# Si5351.net
KiCad netlist of a schematic drawn in EAGLE
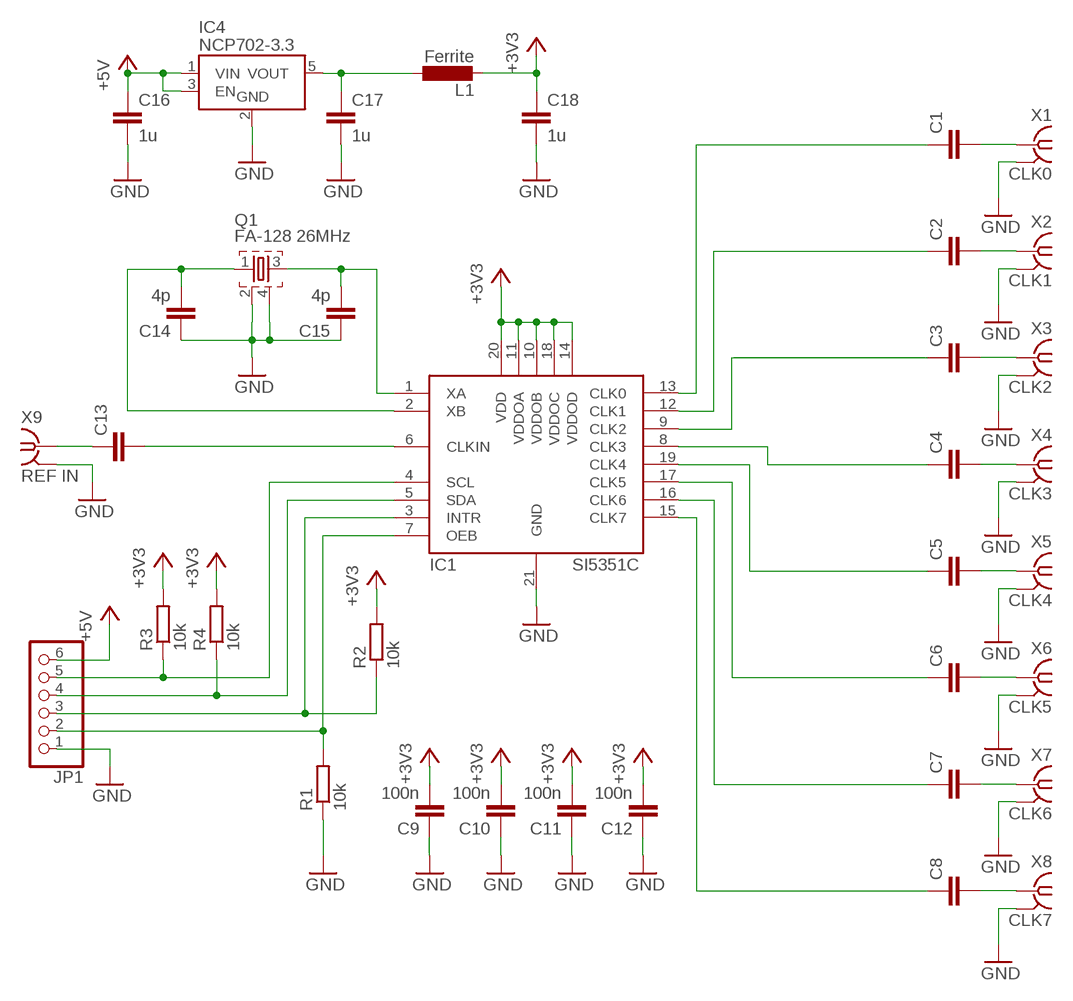
[diagram p0: schematic, sheet 1]

(export (version "E")
  (design (tool "Eeschema 10.0.6"))
  (components
    (comp (ref "C1")
      (value "C-EUC0603")
      (footprint "eagle-import:C0603")
      (libsource (lib "eagle-import") (part "C-EUC0603"))
    )
    (comp (ref "C2")
      (value "C-EUC0603")
      (footprint "eagle-import:C0603")
      (libsource (lib "eagle-import") (part "C-EUC0603"))
    )
    (comp (ref "C3")
      (value "C-EUC0603")
      (footprint "eagle-import:C0603")
      (libsource (lib "eagle-import") (part "C-EUC0603"))
    )
    (comp (ref "C4")
      (value "C-EUC0603")
      (footprint "eagle-import:C0603")
      (libsource (lib "eagle-import") (part "C-EUC0603"))
    )
    (comp (ref "C5")
      (value "C-EUC0603")
      (footprint "eagle-import:C0603")
      (libsource (lib "eagle-import") (part "C-EUC0603"))
    )
    (comp (ref "C6")
      (value "C-EUC0603")
      (footprint "eagle-import:C0603")
      (libsource (lib "eagle-import") (part "C-EUC0603"))
    )
    (comp (ref "C7")
      (value "C-EUC0603")
      (footprint "eagle-import:C0603")
      (libsource (lib "eagle-import") (part "C-EUC0603"))
    )
    (comp (ref "C8")
      (value "C-EUC0603")
      (footprint "eagle-import:C0603")
      (libsource (lib "eagle-import") (part "C-EUC0603"))
    )
    (comp (ref "C9")
      (value "100n")
      (footprint "eagle-import:C0603")
      (libsource (lib "eagle-import") (part "C-EUC0603"))
    )
    (comp (ref "C10")
      (value "100n")
      (footprint "eagle-import:C0603")
      (libsource (lib "eagle-import") (part "C-EUC0603"))
    )
    (comp (ref "C11")
      (value "100n")
      (footprint "eagle-import:C0603")
      (libsource (lib "eagle-import") (part "C-EUC0603"))
    )
    (comp (ref "C12")
      (value "100n")
      (footprint "eagle-import:C0603")
      (libsource (lib "eagle-import") (part "C-EUC0603"))
    )
    (comp (ref "C13")
      (value "C-EUC0603")
      (footprint "eagle-import:C0603")
      (libsource (lib "eagle-import") (part "C-EUC0603"))
    )
    (comp (ref "C14")
      (value "4p")
      (footprint "eagle-import:C0603")
      (libsource (lib "eagle-import") (part "C-EUC0603"))
    )
    (comp (ref "C15")
      (value "4p")
      (footprint "eagle-import:C0603")
      (libsource (lib "eagle-import") (part "C-EUC0603"))
    )
    (comp (ref "C16")
      (value "1u")
      (footprint "eagle-import:C0603")
      (libsource (lib "eagle-import") (part "C-EUC0603"))
    )
    (comp (ref "C17")
      (value "1u")
      (footprint "eagle-import:C0603")
      (libsource (lib "eagle-import") (part "C-EUC0603"))
    )
    (comp (ref "C18")
      (value "1u")
      (footprint "eagle-import:C0603")
      (libsource (lib "eagle-import") (part "C-EUC0603"))
    )
    (comp (ref "IC1")
      (value "SI5351C")
      (footprint "eagle-import:QFN50P400X400X90-21T270N")
      (libsource (lib "eagle-import") (part "SI5351C"))
    )
    (comp (ref "IC4")
      (value "NCP702-3.3")
      (footprint "eagle-import:SOT95P240X110-5")
      (libsource (lib "eagle-import") (part "NCP702"))
    )
    (comp (ref "JP1")
      (value "PINHD-1X6/90")
      (footprint "eagle-import:1X06_90")
      (libsource (lib "eagle-import") (part "PINHD-1X6/90"))
    )
    (comp (ref "L1")
      (value "Ferrite")
      (footprint "eagle-import:R0603")
      (libsource (lib "eagle-import") (part "INDUCTOR0603"))
    )
    (comp (ref "Q1")
      (value "FA-128 26MHz")
      (footprint "eagle-import:FA-128")
      (libsource (lib "eagle-import") (part "FA-128"))
    )
    (comp (ref "R1")
      (value "10k")
      (footprint "eagle-import:R0603")
      (libsource (lib "eagle-import") (part "R-EU_R0603"))
    )
    (comp (ref "R2")
      (value "10k")
      (footprint "eagle-import:R0603")
      (libsource (lib "eagle-import") (part "R-EU_R0603"))
    )
    (comp (ref "R3")
      (value "10k")
      (footprint "eagle-import:R0603")
      (libsource (lib "eagle-import") (part "R-EU_R0603"))
    )
    (comp (ref "R4")
      (value "10k")
      (footprint "eagle-import:R0603")
      (libsource (lib "eagle-import") (part "R-EU_R0603"))
    )
    (comp (ref "X1")
      (value "CLK0")
      (footprint "eagle-import:J502-ND-142-0711-821_826")
      (libsource (lib "eagle-import") (part "SMA_CONNECTOR"))
    )
    (comp (ref "X2")
      (value "CLK1")
      (footprint "eagle-import:J502-ND-142-0711-821_826")
      (libsource (lib "eagle-import") (part "SMA_CONNECTOR"))
    )
    (comp (ref "X3")
      (value "CLK2")
      (footprint "eagle-import:J502-ND-142-0711-821_826")
      (libsource (lib "eagle-import") (part "SMA_CONNECTOR"))
    )
    (comp (ref "X4")
      (value "CLK3")
      (footprint "eagle-import:J502-ND-142-0711-821_826")
      (libsource (lib "eagle-import") (part "SMA_CONNECTOR"))
    )
    (comp (ref "X5")
      (value "CLK4")
      (footprint "eagle-import:J502-ND-142-0711-821_826")
      (libsource (lib "eagle-import") (part "SMA_CONNECTOR"))
    )
    (comp (ref "X6")
      (value "CLK5")
      (footprint "eagle-import:J502-ND-142-0711-821_826")
      (libsource (lib "eagle-import") (part "SMA_CONNECTOR"))
    )
    (comp (ref "X7")
      (value "CLK6")
      (footprint "eagle-import:J502-ND-142-0711-821_826")
      (libsource (lib "eagle-import") (part "SMA_CONNECTOR"))
    )
    (comp (ref "X8")
      (value "CLK7")
      (footprint "eagle-import:J502-ND-142-0711-821_826")
      (libsource (lib "eagle-import") (part "SMA_CONNECTOR"))
    )
    (comp (ref "X9")
      (value "REF IN")
      (footprint "eagle-import:J502-ND-142-0711-821_826")
      (libsource (lib "eagle-import") (part "SMA_CONNECTOR"))
    )
  )
  (nets
    (net (code "1") (name "+3V3") (class "Default")
      (node (ref "C10") (pin "2") (pinfunction "2_2") (pintype "passive"))
      (node (ref "C11") (pin "2") (pinfunction "2_2") (pintype "passive"))
      (node (ref "C12") (pin "2") (pinfunction "2_2") (pintype "passive"))
      (node (ref "C18") (pin "1") (pinfunction "1_1") (pintype "passive"))
      (node (ref "C9") (pin "2") (pinfunction "2_2") (pintype "passive"))
      (node (ref "IC1") (pin "10") (pinfunction "VDDOB_10") (pintype "bidirectional"))
      (node (ref "IC1") (pin "11") (pinfunction "VDDOA_11") (pintype "bidirectional"))
      (node (ref "IC1") (pin "14") (pinfunction "VDDOD_14") (pintype "bidirectional"))
      (node (ref "IC1") (pin "18") (pinfunction "VDDOC_18") (pintype "bidirectional"))
      (node (ref "IC1") (pin "20") (pinfunction "VDD_20") (pintype "bidirectional"))
      (node (ref "L1") (pin "2") (pinfunction "2_2") (pintype "passive"))
      (node (ref "R2") (pin "2") (pinfunction "2_2") (pintype "passive"))
      (node (ref "R3") (pin "2") (pinfunction "2_2") (pintype "passive"))
      (node (ref "R4") (pin "2") (pinfunction "2_2") (pintype "passive"))
    )
    (net (code "2") (name "+5V") (class "Default")
      (node (ref "C16") (pin "1") (pinfunction "1_1") (pintype "passive"))
      (node (ref "IC4") (pin "1") (pinfunction "VIN_1") (pintype "power_in"))
      (node (ref "IC4") (pin "3") (pinfunction "EN_3") (pintype "input"))
      (node (ref "JP1") (pin "6") (pinfunction "6_6") (pintype "passive"))
    )
    (net (code "3") (name "GND") (class "Default")
      (node (ref "C10") (pin "1") (pinfunction "1_1") (pintype "passive"))
      (node (ref "C11") (pin "1") (pinfunction "1_1") (pintype "passive"))
      (node (ref "C12") (pin "1") (pinfunction "1_1") (pintype "passive"))
      (node (ref "C14") (pin "1") (pinfunction "1_1") (pintype "passive"))
      (node (ref "C15") (pin "1") (pinfunction "1_1") (pintype "passive"))
      (node (ref "C16") (pin "2") (pinfunction "2_2") (pintype "passive"))
      (node (ref "C17") (pin "2") (pinfunction "2_2") (pintype "passive"))
      (node (ref "C18") (pin "2") (pinfunction "2_2") (pintype "passive"))
      (node (ref "C9") (pin "1") (pinfunction "1_1") (pintype "passive"))
      (node (ref "IC1") (pin "21") (pinfunction "GND_21") (pintype "bidirectional"))
      (node (ref "IC4") (pin "2") (pinfunction "GND_2") (pintype "power_in"))
      (node (ref "JP1") (pin "1") (pinfunction "1_1") (pintype "passive"))
      (node (ref "Q1") (pin "2") (pinfunction "2_2") (pintype "passive"))
      (node (ref "Q1") (pin "4") (pinfunction "4_4") (pintype "passive"))
      (node (ref "R1") (pin "1") (pinfunction "1_1") (pintype "passive"))
      (node (ref "X1") (pin "G@1") (pinfunction "2_G@1") (pintype "passive"))
      (node (ref "X1") (pin "G@2") (pinfunction "2_G@2") (pintype "passive"))
      (node (ref "X1") (pin "G@3") (pinfunction "2_G@3") (pintype "passive"))
      (node (ref "X1") (pin "G@4") (pinfunction "2_G@4") (pintype "passive"))
      (node (ref "X2") (pin "G@1") (pinfunction "2_G@1") (pintype "passive"))
      (node (ref "X2") (pin "G@2") (pinfunction "2_G@2") (pintype "passive"))
      (node (ref "X2") (pin "G@3") (pinfunction "2_G@3") (pintype "passive"))
      (node (ref "X2") (pin "G@4") (pinfunction "2_G@4") (pintype "passive"))
      (node (ref "X3") (pin "G@1") (pinfunction "2_G@1") (pintype "passive"))
      (node (ref "X3") (pin "G@2") (pinfunction "2_G@2") (pintype "passive"))
      (node (ref "X3") (pin "G@3") (pinfunction "2_G@3") (pintype "passive"))
      (node (ref "X3") (pin "G@4") (pinfunction "2_G@4") (pintype "passive"))
      (node (ref "X4") (pin "G@1") (pinfunction "2_G@1") (pintype "passive"))
      (node (ref "X4") (pin "G@2") (pinfunction "2_G@2") (pintype "passive"))
      (node (ref "X4") (pin "G@3") (pinfunction "2_G@3") (pintype "passive"))
      (node (ref "X4") (pin "G@4") (pinfunction "2_G@4") (pintype "passive"))
      (node (ref "X5") (pin "G@1") (pinfunction "2_G@1") (pintype "passive"))
      (node (ref "X5") (pin "G@2") (pinfunction "2_G@2") (pintype "passive"))
      (node (ref "X5") (pin "G@3") (pinfunction "2_G@3") (pintype "passive"))
      (node (ref "X5") (pin "G@4") (pinfunction "2_G@4") (pintype "passive"))
      (node (ref "X6") (pin "G@1") (pinfunction "2_G@1") (pintype "passive"))
      (node (ref "X6") (pin "G@2") (pinfunction "2_G@2") (pintype "passive"))
      (node (ref "X6") (pin "G@3") (pinfunction "2_G@3") (pintype "passive"))
      (node (ref "X6") (pin "G@4") (pinfunction "2_G@4") (pintype "passive"))
      (node (ref "X7") (pin "G@1") (pinfunction "2_G@1") (pintype "passive"))
      (node (ref "X7") (pin "G@2") (pinfunction "2_G@2") (pintype "passive"))
      (node (ref "X7") (pin "G@3") (pinfunction "2_G@3") (pintype "passive"))
      (node (ref "X7") (pin "G@4") (pinfunction "2_G@4") (pintype "passive"))
      (node (ref "X8") (pin "G@1") (pinfunction "2_G@1") (pintype "passive"))
      (node (ref "X8") (pin "G@2") (pinfunction "2_G@2") (pintype "passive"))
      (node (ref "X8") (pin "G@3") (pinfunction "2_G@3") (pintype "passive"))
      (node (ref "X8") (pin "G@4") (pinfunction "2_G@4") (pintype "passive"))
      (node (ref "X9") (pin "G@1") (pinfunction "2_G@1") (pintype "passive"))
      (node (ref "X9") (pin "G@2") (pinfunction "2_G@2") (pintype "passive"))
      (node (ref "X9") (pin "G@3") (pinfunction "2_G@3") (pintype "passive"))
      (node (ref "X9") (pin "G@4") (pinfunction "2_G@4") (pintype "passive"))
    )
    (net (code "4") (name "Net-(C1-Pad2)") (class "Default")
      (node (ref "C1") (pin "2") (pinfunction "2_2") (pintype "passive"))
      (node (ref "X1") (pin "1") (pinfunction "1_1") (pintype "passive"))
    )
    (net (code "5") (name "Net-(C2-Pad2)") (class "Default")
      (node (ref "C2") (pin "2") (pinfunction "2_2") (pintype "passive"))
      (node (ref "X2") (pin "1") (pinfunction "1_1") (pintype "passive"))
    )
    (net (code "6") (name "Net-(C3-Pad2)") (class "Default")
      (node (ref "C3") (pin "2") (pinfunction "2_2") (pintype "passive"))
      (node (ref "X3") (pin "1") (pinfunction "1_1") (pintype "passive"))
    )
    (net (code "7") (name "Net-(C4-Pad2)") (class "Default")
      (node (ref "C4") (pin "2") (pinfunction "2_2") (pintype "passive"))
      (node (ref "X4") (pin "1") (pinfunction "1_1") (pintype "passive"))
    )
    (net (code "8") (name "Net-(C5-Pad2)") (class "Default")
      (node (ref "C5") (pin "2") (pinfunction "2_2") (pintype "passive"))
      (node (ref "X5") (pin "1") (pinfunction "1_1") (pintype "passive"))
    )
    (net (code "9") (name "Net-(C6-Pad2)") (class "Default")
      (node (ref "C6") (pin "2") (pinfunction "2_2") (pintype "passive"))
      (node (ref "X6") (pin "1") (pinfunction "1_1") (pintype "passive"))
    )
    (net (code "10") (name "Net-(C7-Pad2)") (class "Default")
      (node (ref "C7") (pin "2") (pinfunction "2_2") (pintype "passive"))
      (node (ref "X7") (pin "1") (pinfunction "1_1") (pintype "passive"))
    )
    (net (code "11") (name "Net-(C8-Pad2)") (class "Default")
      (node (ref "C8") (pin "2") (pinfunction "2_2") (pintype "passive"))
      (node (ref "X8") (pin "1") (pinfunction "1_1") (pintype "passive"))
    )
    (net (code "12") (name "Net-(C13-Pad1)") (class "Default")
      (node (ref "C13") (pin "1") (pinfunction "1_1") (pintype "passive"))
      (node (ref "X9") (pin "1") (pinfunction "1_1") (pintype "passive"))
    )
    (net (code "13") (name "Net-(IC1-CLK0)") (class "Default")
      (node (ref "C1") (pin "1") (pinfunction "1_1") (pintype "passive"))
      (node (ref "IC1") (pin "13") (pinfunction "CLK0_13") (pintype "bidirectional"))
    )
    (net (code "14") (name "Net-(IC1-CLK1)") (class "Default")
      (node (ref "C2") (pin "1") (pinfunction "1_1") (pintype "passive"))
      (node (ref "IC1") (pin "12") (pinfunction "CLK1_12") (pintype "bidirectional"))
    )
    (net (code "15") (name "Net-(IC1-CLK2)") (class "Default")
      (node (ref "C3") (pin "1") (pinfunction "1_1") (pintype "passive"))
      (node (ref "IC1") (pin "9") (pinfunction "CLK2_9") (pintype "bidirectional"))
    )
    (net (code "16") (name "Net-(IC1-CLK3)") (class "Default")
      (node (ref "C4") (pin "1") (pinfunction "1_1") (pintype "passive"))
      (node (ref "IC1") (pin "8") (pinfunction "CLK3_8") (pintype "bidirectional"))
    )
    (net (code "17") (name "Net-(IC1-CLK4)") (class "Default")
      (node (ref "C5") (pin "1") (pinfunction "1_1") (pintype "passive"))
      (node (ref "IC1") (pin "19") (pinfunction "CLK4_19") (pintype "bidirectional"))
    )
    (net (code "18") (name "Net-(IC1-CLK5)") (class "Default")
      (node (ref "C6") (pin "1") (pinfunction "1_1") (pintype "passive"))
      (node (ref "IC1") (pin "17") (pinfunction "CLK5_17") (pintype "bidirectional"))
    )
    (net (code "19") (name "Net-(IC1-CLK6)") (class "Default")
      (node (ref "C7") (pin "1") (pinfunction "1_1") (pintype "passive"))
      (node (ref "IC1") (pin "16") (pinfunction "CLK6_16") (pintype "bidirectional"))
    )
    (net (code "20") (name "Net-(IC1-CLK7)") (class "Default")
      (node (ref "C8") (pin "1") (pinfunction "1_1") (pintype "passive"))
      (node (ref "IC1") (pin "15") (pinfunction "CLK7_15") (pintype "bidirectional"))
    )
    (net (code "21") (name "Net-(IC1-CLKIN)") (class "Default")
      (node (ref "C13") (pin "2") (pinfunction "2_2") (pintype "passive"))
      (node (ref "IC1") (pin "6") (pinfunction "CLKIN_6") (pintype "bidirectional"))
    )
    (net (code "22") (name "Net-(IC1-INTR)") (class "Default")
      (node (ref "IC1") (pin "3") (pinfunction "INTR_3") (pintype "bidirectional"))
      (node (ref "JP1") (pin "3") (pinfunction "3_3") (pintype "passive"))
      (node (ref "R2") (pin "1") (pinfunction "1_1") (pintype "passive"))
    )
    (net (code "23") (name "Net-(IC1-OEB)") (class "Default")
      (node (ref "IC1") (pin "7") (pinfunction "OEB_7") (pintype "bidirectional"))
      (node (ref "JP1") (pin "2") (pinfunction "2_2") (pintype "passive"))
      (node (ref "R1") (pin "2") (pinfunction "2_2") (pintype "passive"))
    )
    (net (code "24") (name "Net-(IC1-SCL)") (class "Default")
      (node (ref "IC1") (pin "4") (pinfunction "SCL_4") (pintype "bidirectional"))
      (node (ref "JP1") (pin "5") (pinfunction "5_5") (pintype "passive"))
      (node (ref "R3") (pin "1") (pinfunction "1_1") (pintype "passive"))
    )
    (net (code "25") (name "Net-(IC1-SDA)") (class "Default")
      (node (ref "IC1") (pin "5") (pinfunction "SDA_5") (pintype "bidirectional"))
      (node (ref "JP1") (pin "4") (pinfunction "4_4") (pintype "passive"))
      (node (ref "R4") (pin "1") (pinfunction "1_1") (pintype "passive"))
    )
    (net (code "26") (name "Net-(IC1-XA)") (class "Default")
      (node (ref "C15") (pin "2") (pinfunction "2_2") (pintype "passive"))
      (node (ref "IC1") (pin "1") (pinfunction "XA_1") (pintype "bidirectional"))
      (node (ref "Q1") (pin "3") (pinfunction "3_3") (pintype "passive"))
    )
    (net (code "27") (name "Net-(IC1-XB)") (class "Default")
      (node (ref "C14") (pin "2") (pinfunction "2_2") (pintype "passive"))
      (node (ref "IC1") (pin "2") (pinfunction "XB_2") (pintype "bidirectional"))
      (node (ref "Q1") (pin "1") (pinfunction "1_1") (pintype "passive"))
    )
    (net (code "28") (name "Net-(IC4-VOUT)") (class "Default")
      (node (ref "C17") (pin "1") (pinfunction "1_1") (pintype "passive"))
      (node (ref "IC4") (pin "5") (pinfunction "VOUT_5") (pintype "power_in"))
      (node (ref "L1") (pin "1") (pinfunction "1_1") (pintype "passive"))
    )
  )
)
